# Sitara_AUX.net
KiCad netlist of a schematic drawn in Altium Designer
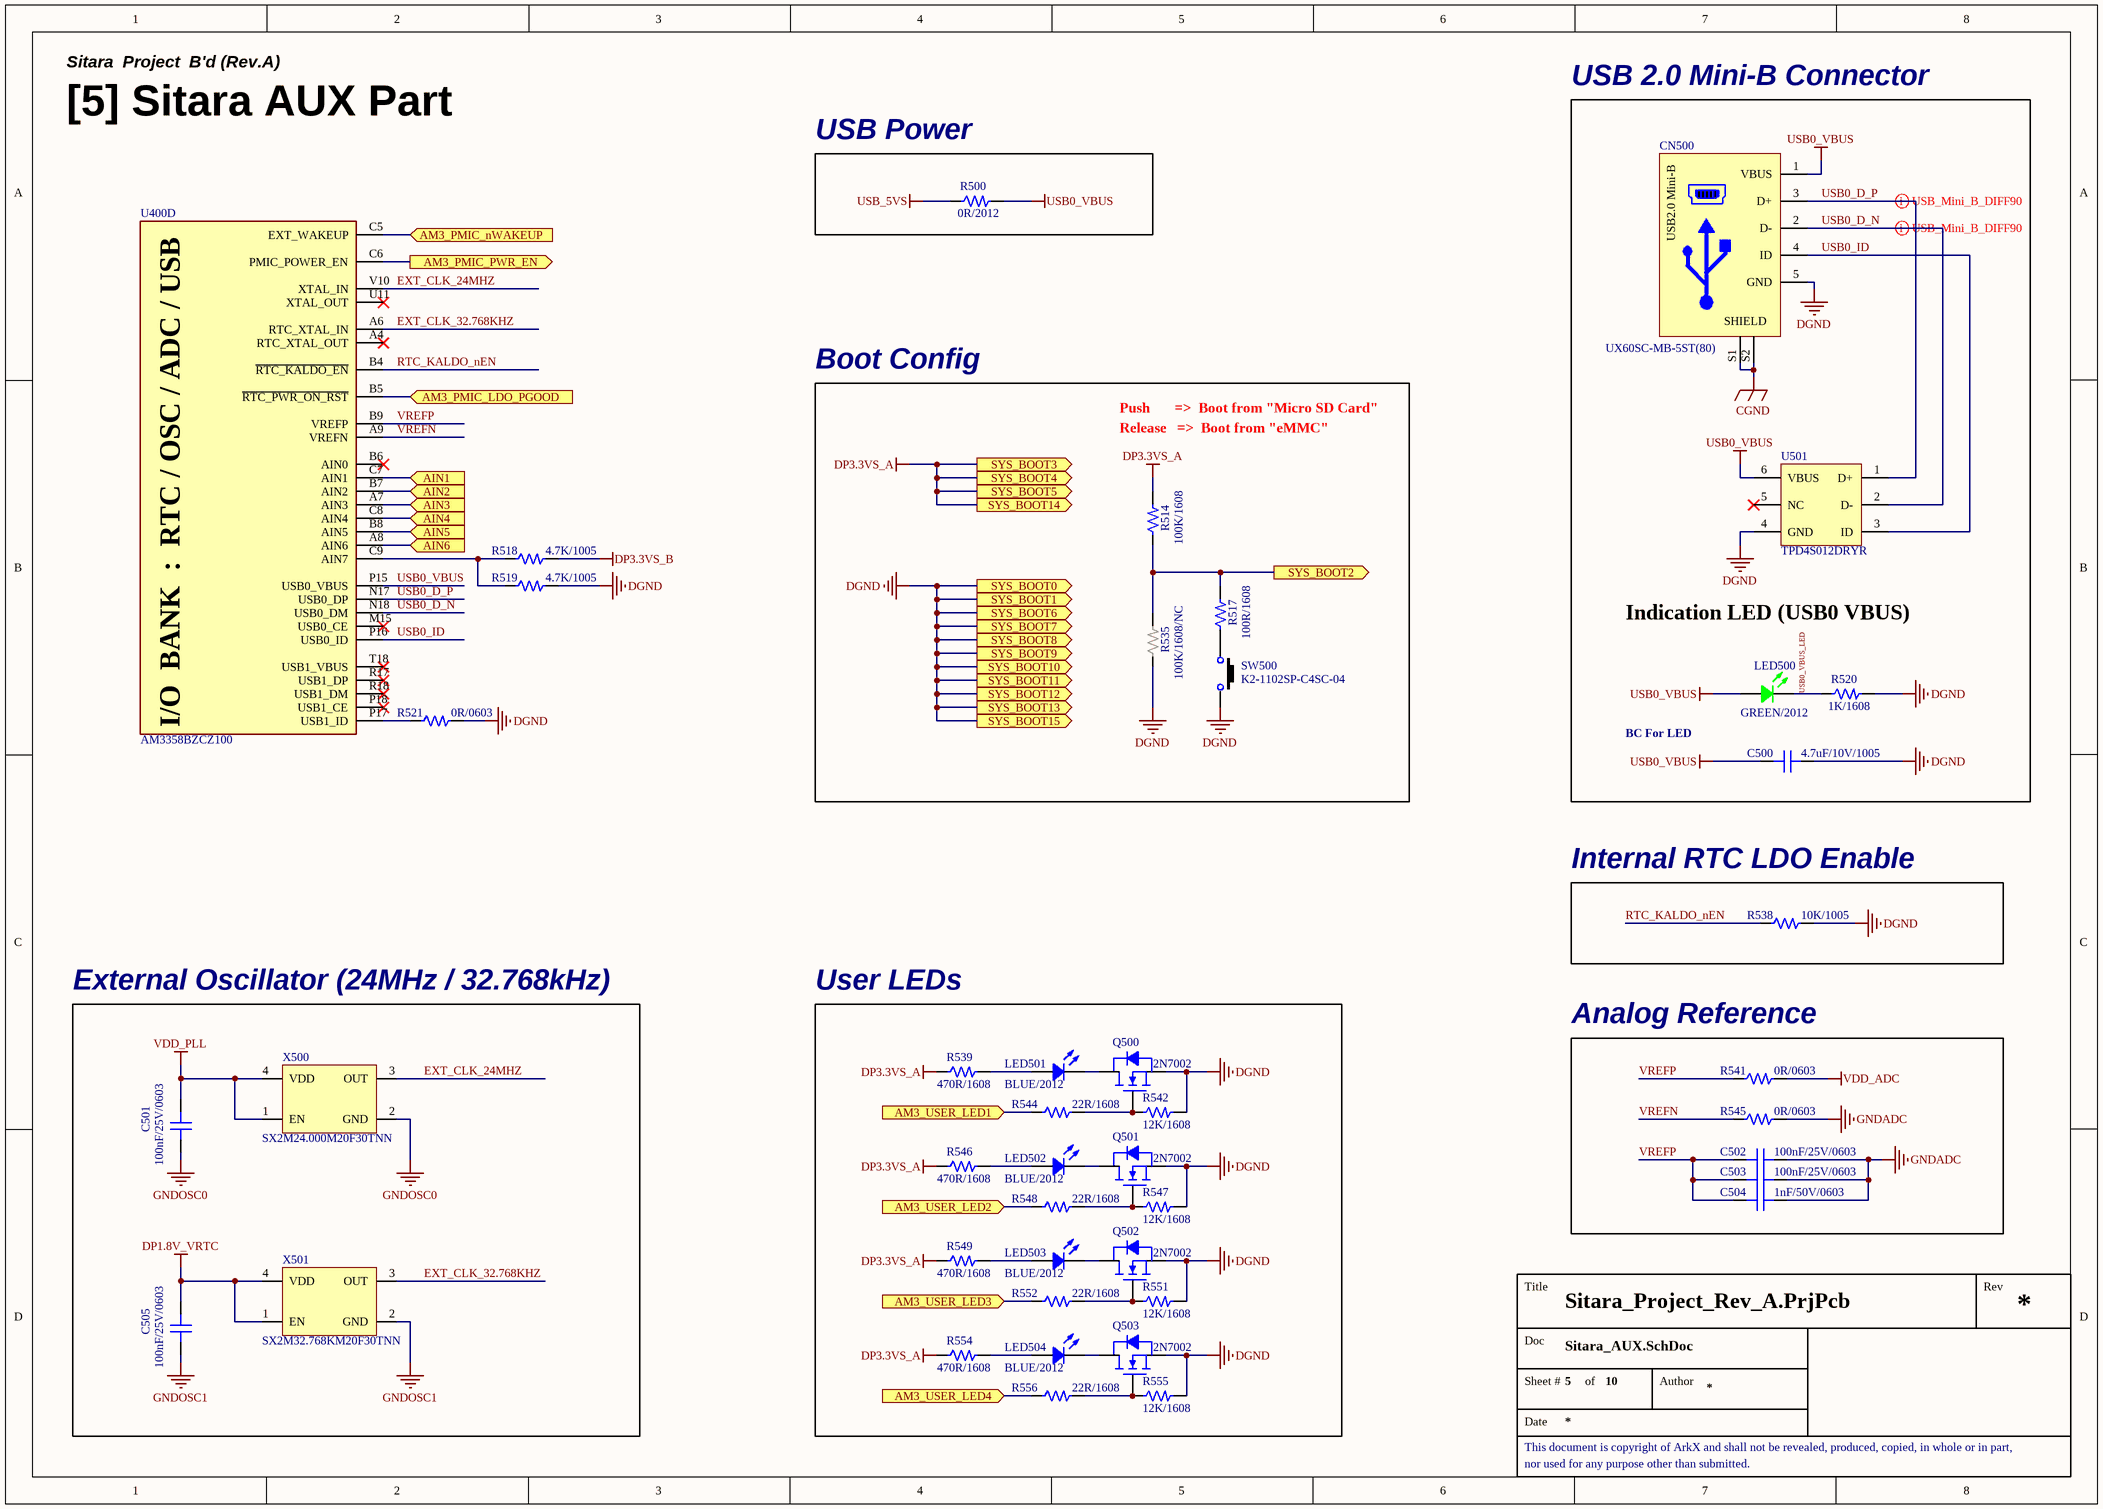
[diagram p0: Sitara_AUX.SchDoc]

(export (version "E")
  (design (tool "Eeschema 10.0.6"))
  (components
    (comp (ref "C500")
      (value "4.7uF/10V/1005")
      (footprint "CAP 1005 (0402_INCH)")
      (description "10V 4.7uF X5R ±20% 0402  Multilayer Ceramic Capacitors MLCC - SMD/SMT ROHS")
      (fields (field (name "LCSC PART #") "C23733"))
      (libsource (lib "Arkx") (part "CAP_4.7uF/10V/1005"))
    )
    (comp (ref "C501")
      (value "100nF/25V/0603")
      (footprint "CAP 0603 (0201_INCH)")
      (description "Ceramic CAP_100nF/25V/0603")
      (fields (field (name "LCSC PART #") "C181047"))
      (libsource (lib "Arkx") (part "CAP_100nF/25V/0603"))
    )
    (comp (ref "C502")
      (value "100nF/25V/0603")
      (footprint "CAP 0603 (0201_INCH)")
      (description "Ceramic CAP_100nF/25V/0603")
      (fields (field (name "LCSC PART #") "C181047"))
      (libsource (lib "Arkx") (part "CAP_100nF/25V/0603"))
    )
    (comp (ref "C503")
      (value "100nF/25V/0603")
      (footprint "CAP 0603 (0201_INCH)")
      (description "Ceramic CAP_100nF/25V/0603")
      (fields (field (name "LCSC PART #") "C181047"))
      (libsource (lib "Arkx") (part "CAP_100nF/25V/0603"))
    )
    (comp (ref "C504")
      (value "1nF/50V/0603")
      (footprint "CAP 0603 (0201_INCH)")
      (description "Ceramic CAP_1nF/50V/0603")
      (fields (field (name "LCSC PART #") "C85934"))
      (libsource (lib "Arkx") (part "CAP_1nF/50V/0603"))
    )
    (comp (ref "C505")
      (value "100nF/25V/0603")
      (footprint "CAP 0603 (0201_INCH)")
      (description "Ceramic CAP_100nF/25V/0603")
      (fields (field (name "LCSC PART #") "C181047"))
      (libsource (lib "Arkx") (part "CAP_100nF/25V/0603"))
    )
    (comp (ref "CN500")
      (value "UX60SC-MB-5ST(80)")
      (footprint "CON_USB2.0-Mini-B (UX60SC-MB-5ST(80))")
      (description "USB - mini B USB 2.0 Receptacle Connector 5 Position Surface Mount, Right Angle")
      (fields (field (name "LCSC PART #") "C2692070"))
      (libsource (lib "Arkx") (part "CON_USB2.0-Mini-B"))
    )
    (comp (ref "LED500")
      (value "GREEN/2012")
      (footprint "LED MHT170RGBCT (GREEN)")
      (fields (field (name "LCSC PART #") "C2962094"))
      (libsource (lib "Arkx") (part "LED_MHT170RGBCT(GREEN)"))
    )
    (comp (ref "LED501")
      (value "BLUE/2012")
      (footprint "LED MHT170RGBCT (BLUE)")
      (fields (field (name "LCSC PART #") "C2962094"))
      (libsource (lib "Arkx") (part "LED_MHT170RGBCT(BLUE)"))
    )
    (comp (ref "LED502")
      (value "BLUE/2012")
      (footprint "LED MHT170RGBCT (BLUE)")
      (fields (field (name "LCSC PART #") "C2962094"))
      (libsource (lib "Arkx") (part "LED_MHT170RGBCT(BLUE)"))
    )
    (comp (ref "LED503")
      (value "BLUE/2012")
      (footprint "LED MHT170RGBCT (BLUE)")
      (fields (field (name "LCSC PART #") "C2962094"))
      (libsource (lib "Arkx") (part "LED_MHT170RGBCT(BLUE)"))
    )
    (comp (ref "LED504")
      (value "BLUE/2012")
      (footprint "LED MHT170RGBCT (BLUE)")
      (fields (field (name "LCSC PART #") "C2962094"))
      (libsource (lib "Arkx") (part "LED_MHT170RGBCT(BLUE)"))
    )
    (comp (ref "Q500")
      (value "2N7002")
      (footprint "SOT 23-3 (DIODES INCORPORATED)")
      (description "60V 115mA 200mW 7.5Ω@10V,500mA N Channel SOT-23  MOSFETs ROHS")
      (fields (field (name "LCSC PART #") "C8545"))
      (libsource (lib "Arkx") (part "FET_2N7002"))
    )
    (comp (ref "Q501")
      (value "2N7002")
      (footprint "SOT 23-3 (DIODES INCORPORATED)")
      (description "60V 115mA 200mW 7.5Ω@10V,500mA N Channel SOT-23  MOSFETs ROHS")
      (fields (field (name "LCSC PART #") "C8545"))
      (libsource (lib "Arkx") (part "FET_2N7002"))
    )
    (comp (ref "Q502")
      (value "2N7002")
      (footprint "SOT 23-3 (DIODES INCORPORATED)")
      (description "60V 115mA 200mW 7.5Ω@10V,500mA N Channel SOT-23  MOSFETs ROHS")
      (fields (field (name "LCSC PART #") "C8545"))
      (libsource (lib "Arkx") (part "FET_2N7002"))
    )
    (comp (ref "Q503")
      (value "2N7002")
      (footprint "SOT 23-3 (DIODES INCORPORATED)")
      (description "60V 115mA 200mW 7.5Ω@10V,500mA N Channel SOT-23  MOSFETs ROHS")
      (fields (field (name "LCSC PART #") "C8545"))
      (libsource (lib "Arkx") (part "FET_2N7002"))
    )
    (comp (ref "R500")
      (value "0R/2012")
      (footprint "RES 2012 (0805_inch)")
      (description "RES_0R/2012/0.125W")
      (fields (field (name "LCSC PART #") "C17477"))
      (libsource (lib "Arkx") (part "RES_0R/2012/0.125W"))
    )
    (comp (ref "R514")
      (value "100K/1608")
      (footprint "RES 1608 (0603_inch)")
      (description "RES_100K/1608/0.1W")
      (fields (field (name "LCSC PART #") "C25803"))
      (libsource (lib "Arkx") (part "RES_100K/1608/0.1W"))
    )
    (comp (ref "R517")
      (value "100R/1608")
      (footprint "RES 1608 (0603_inch)")
      (description "RES_100R/1608/0.1W")
      (fields (field (name "LCSC PART #") "C22775"))
      (libsource (lib "Arkx") (part "RES_100R/1608/0.1W"))
    )
    (comp (ref "R518")
      (value "4.7K/1005")
      (footprint "RES 1005 (0402_inch)")
      (description "RES_4.7K/1005/62.5mW")
      (fields (field (name "LCSC PART #") "C25900"))
      (libsource (lib "Arkx") (part "RES_4.7K/1005/62.5mW"))
    )
    (comp (ref "R519")
      (value "4.7K/1005")
      (footprint "RES 1005 (0402_inch)")
      (description "RES_4.7K/1005/62.5mW")
      (fields (field (name "LCSC PART #") "C25900"))
      (libsource (lib "Arkx") (part "RES_4.7K/1005/62.5mW"))
    )
    (comp (ref "R520")
      (value "1K/1608")
      (footprint "RES 1608 (0603_inch)")
      (description "RES_1K/1608/0.1W")
      (fields (field (name "LCSC PART #") "C21190"))
      (libsource (lib "Arkx") (part "RES_1K/1608/0.1W"))
    )
    (comp (ref "R521")
      (value "0R/0603")
      (footprint "RES 0603 (0201_inch)")
      (description "50mW Thick Film Resistors 25V ±1% 0Ω 0201  Chip Resistor - Surface Mount ROHS")
      (fields (field (name "LCSC PART #") "C106227"))
      (libsource (lib "Arkx") (part "RES_0R/0603/50mW"))
    )
    (comp (ref "R535")
      (value "100K/1608/NC")
      (footprint "RES 1608 (0603_inch)/NC")
      (description "RES_100K/1608/0.1W")
      (libsource (lib "Arkx") (part "RES_NC_100K/1608/0.1W"))
    )
    (comp (ref "R538")
      (value "10K/1005")
      (footprint "RES 1005 (0402_inch)")
      (description "RES_10K/1005/62.5mW")
      (fields (field (name "LCSC PART #") "C25744"))
      (libsource (lib "Arkx") (part "RES_10K/1005/62.5mW"))
    )
    (comp (ref "R539")
      (value "470R/1608")
      (footprint "RES 1608 (0603_inch)")
      (description "RES_470R/1608/0.1W")
      (fields (field (name "LCSC PART #") "C23179"))
      (libsource (lib "Arkx") (part "RES_470R/1608/0.1W"))
    )
    (comp (ref "R541")
      (value "0R/0603")
      (footprint "RES 0603 (0201_inch)")
      (description "50mW Thick Film Resistors 25V ±1% 0Ω 0201  Chip Resistor - Surface Mount ROHS")
      (fields (field (name "LCSC PART #") "C106227"))
      (libsource (lib "Arkx") (part "RES_0R/0603/50mW"))
    )
    (comp (ref "R542")
      (value "12K/1608")
      (footprint "RES 1608 (0603_inch)")
      (description "RES_12K/1608/0.1W")
      (fields (field (name "LCSC PART #") "C22790"))
      (libsource (lib "Arkx") (part "RES_12K/1608/0.1W"))
    )
    (comp (ref "R544")
      (value "22R/1608")
      (footprint "RES 1608 (0603_inch)")
      (description "RES_22R/1608/0.1W")
      (fields (field (name "LCSC PART #") "C23345"))
      (libsource (lib "Arkx") (part "RES_22R/1608/0.1W"))
    )
    (comp (ref "R545")
      (value "0R/0603")
      (footprint "RES 0603 (0201_inch)")
      (description "50mW Thick Film Resistors 25V ±1% 0Ω 0201  Chip Resistor - Surface Mount ROHS")
      (fields (field (name "LCSC PART #") "C106227"))
      (libsource (lib "Arkx") (part "RES_0R/0603/50mW"))
    )
    (comp (ref "R546")
      (value "470R/1608")
      (footprint "RES 1608 (0603_inch)")
      (description "RES_470R/1608/0.1W")
      (fields (field (name "LCSC PART #") "C23179"))
      (libsource (lib "Arkx") (part "RES_470R/1608/0.1W"))
    )
    (comp (ref "R547")
      (value "12K/1608")
      (footprint "RES 1608 (0603_inch)")
      (description "RES_12K/1608/0.1W")
      (fields (field (name "LCSC PART #") "C22790"))
      (libsource (lib "Arkx") (part "RES_12K/1608/0.1W"))
    )
    (comp (ref "R548")
      (value "22R/1608")
      (footprint "RES 1608 (0603_inch)")
      (description "RES_22R/1608/0.1W")
      (fields (field (name "LCSC PART #") "C23345"))
      (libsource (lib "Arkx") (part "RES_22R/1608/0.1W"))
    )
    (comp (ref "R549")
      (value "470R/1608")
      (footprint "RES 1608 (0603_inch)")
      (description "RES_470R/1608/0.1W")
      (fields (field (name "LCSC PART #") "C23179"))
      (libsource (lib "Arkx") (part "RES_470R/1608/0.1W"))
    )
    (comp (ref "R551")
      (value "12K/1608")
      (footprint "RES 1608 (0603_inch)")
      (description "RES_12K/1608/0.1W")
      (fields (field (name "LCSC PART #") "C22790"))
      (libsource (lib "Arkx") (part "RES_12K/1608/0.1W"))
    )
    (comp (ref "R552")
      (value "22R/1608")
      (footprint "RES 1608 (0603_inch)")
      (description "RES_22R/1608/0.1W")
      (fields (field (name "LCSC PART #") "C23345"))
      (libsource (lib "Arkx") (part "RES_22R/1608/0.1W"))
    )
    (comp (ref "R554")
      (value "470R/1608")
      (footprint "RES 1608 (0603_inch)")
      (description "RES_470R/1608/0.1W")
      (fields (field (name "LCSC PART #") "C23179"))
      (libsource (lib "Arkx") (part "RES_470R/1608/0.1W"))
    )
    (comp (ref "R555")
      (value "12K/1608")
      (footprint "RES 1608 (0603_inch)")
      (description "RES_12K/1608/0.1W")
      (fields (field (name "LCSC PART #") "C22790"))
      (libsource (lib "Arkx") (part "RES_12K/1608/0.1W"))
    )
    (comp (ref "R556")
      (value "22R/1608")
      (footprint "RES 1608 (0603_inch)")
      (description "RES_22R/1608/0.1W")
      (fields (field (name "LCSC PART #") "C23345"))
      (libsource (lib "Arkx") (part "RES_22R/1608/0.1W"))
    )
    (comp (ref "SW500")
      (value "K2-1102SP-C4SC-04")
      (footprint "SW K2-1102SP-C4SC-04")
      (fields (field (name "LCSC PART #") "C127509"))
      (libsource (lib "Arkx") (part "SW_K2-1102SP-C4SC-04(2P)"))
    )
    (comp (ref "U400")
      (value "AM3358BZCZ100")
      (footprint "IC_SOC_AM3358BZCZ100")
      (description "ARM® Cortex®-A8 Microprocessor IC Sitara™ 1 Core, 32-Bit 1.0GHz 324-NFBGA (15x15)")
      (fields (field (name "LCSC PART #") "C73932"))
      (libsource (lib "Arkx") (part "IC_SOC_AM3358BZCZ100"))
    )
    (comp (ref "U501")
      (value "TPD4S012DRYR")
      (footprint "IC_SON-6")
      (description "Clamp 3A (8/20µs) Ipp Tvs Diode Surface Mount 6-SON (1.45x1)")
      (fields (field (name "LCSC PART #") "C96506"))
      (libsource (lib "Arkx") (part "DIO_TVS_TPD4S012DRYR"))
    )
    (comp (ref "X500")
      (value "SX2M24.000M20F30TNN")
      (footprint "OSC SMD_2.5x2.0 (SCTF)")
      (description "1.62V~3.63V ±20ppm 10mA ±30ppm CMOS 24MHz SMD2520-4P  Crystal Oscillators ROHS")
      (fields (field (name "LCSC PART #") "C2901600"))
      (libsource (lib "Arkx") (part "OSC_SX2M24.000M20F30TNN(24MHz)"))
    )
    (comp (ref "X501")
      (value "SX2M32.768KM20F30TNN")
      (footprint "OSC SMD_2.5x2.0 (SCTF)")
      (description "1.62V~3.63V ±20ppm 90uA ±30ppm CMOS 32.768kHz SMD2520-4P  Crystal Oscillators ROHS")
      (fields (field (name "LCSC PART #") "C2901603"))
      (libsource (lib "Arkx") (part "OSC_SX2M32.768KM20F30TNN(32.768kHz)"))
    )
  )
  (nets
    (net (code "1") (name "/AIN1") (class "Default")
      (node (ref "U400") (pin "C7") (pinfunction "AIN1_C7") (pintype "passive"))
    )
    (net (code "2") (name "/AIN2") (class "Default")
      (node (ref "U400") (pin "B7") (pinfunction "AIN2_B7") (pintype "passive"))
    )
    (net (code "3") (name "/AIN3") (class "Default")
      (node (ref "U400") (pin "A7") (pinfunction "AIN3_A7") (pintype "passive"))
    )
    (net (code "4") (name "/AIN4") (class "Default")
      (node (ref "U400") (pin "C8") (pinfunction "AIN4_C8") (pintype "passive"))
    )
    (net (code "5") (name "/AIN5") (class "Default")
      (node (ref "U400") (pin "B8") (pinfunction "AIN5_B8") (pintype "passive"))
    )
    (net (code "6") (name "/AIN6") (class "Default")
      (node (ref "U400") (pin "A8") (pinfunction "AIN6_A8") (pintype "passive"))
    )
    (net (code "7") (name "/AM3_PMIC_LDO_PGOOD") (class "Default")
      (node (ref "U400") (pin "B5") (pinfunction "~{RTC_PWR_ON_RST}_B5") (pintype "passive"))
    )
    (net (code "8") (name "/AM3_PMIC_PWR_EN") (class "Default")
      (node (ref "U400") (pin "C6") (pinfunction "PMIC_POWER_EN_C6") (pintype "passive"))
    )
    (net (code "9") (name "/AM3_PMIC_nWAKEUP") (class "Default")
      (node (ref "U400") (pin "C5") (pinfunction "EXT_WAKEUP_C5") (pintype "passive"))
    )
    (net (code "10") (name "/AM3_USER_LED1") (class "Default")
      (node (ref "R544") (pin "1") (pinfunction "1_1") (pintype "passive"))
    )
    (net (code "11") (name "/AM3_USER_LED2") (class "Default")
      (node (ref "R548") (pin "1") (pinfunction "1_1") (pintype "passive"))
    )
    (net (code "12") (name "/AM3_USER_LED3") (class "Default")
      (node (ref "R552") (pin "1") (pinfunction "1_1") (pintype "passive"))
    )
    (net (code "13") (name "/AM3_USER_LED4") (class "Default")
      (node (ref "R556") (pin "1") (pinfunction "1_1") (pintype "passive"))
    )
    (net (code "14") (name "/EXT_CLK_24MHZ") (class "Default")
      (node (ref "U400") (pin "V10") (pinfunction "XTAL_IN_V10") (pintype "passive"))
      (node (ref "X500") (pin "3") (pinfunction "OUT_3") (pintype "passive"))
    )
    (net (code "15") (name "/EXT_CLK_32.768KHZ") (class "Default")
      (node (ref "U400") (pin "A6") (pinfunction "RTC_XTAL_IN_A6") (pintype "passive"))
      (node (ref "X501") (pin "3") (pinfunction "OUT_3") (pintype "passive"))
    )
    (net (code "16") (name "/RTC_KALDO_nEN") (class "Default")
      (node (ref "R538") (pin "1") (pinfunction "1_1") (pintype "passive"))
      (node (ref "U400") (pin "B4") (pinfunction "~{RTC_KALDO_EN}_B4") (pintype "passive"))
    )
    (net (code "17") (name "/SYS_BOOT2") (class "Default")
      (node (ref "R514") (pin "1") (pinfunction "1_1") (pintype "passive"))
      (node (ref "R517") (pin "2") (pinfunction "2_2") (pintype "passive"))
      (node (ref "R535") (pin "2") (pinfunction "2_2") (pintype "passive"))
    )
    (net (code "18") (name "/USB0_D_N") (class "Default")
      (node (ref "CN500") (pin "2") (pinfunction "D-_2") (pintype "passive"))
      (node (ref "U400") (pin "N18") (pinfunction "USB0_DM_N18") (pintype "passive"))
      (node (ref "U501") (pin "2") (pinfunction "D-_2") (pintype "passive"))
    )
    (net (code "19") (name "/USB0_D_P") (class "Default")
      (node (ref "CN500") (pin "3") (pinfunction "D+_3") (pintype "passive"))
      (node (ref "U400") (pin "N17") (pinfunction "USB0_DP_N17") (pintype "passive"))
      (node (ref "U501") (pin "1") (pinfunction "D+_1") (pintype "passive"))
    )
    (net (code "20") (name "/USB0_ID") (class "Default")
      (node (ref "CN500") (pin "4") (pinfunction "ID_4") (pintype "passive"))
      (node (ref "U400") (pin "P16") (pinfunction "USB0_ID_P16") (pintype "passive"))
      (node (ref "U501") (pin "3") (pinfunction "ID_3") (pintype "passive"))
    )
    (net (code "21") (name "/USB0_VBUS_LED") (class "Default")
      (node (ref "LED500") (pin "2") (pinfunction "GREEN_2") (pintype "passive"))
      (node (ref "R520") (pin "1") (pinfunction "1_1") (pintype "passive"))
    )
    (net (code "22") (name "/VREFN") (class "Default")
      (node (ref "R545") (pin "1") (pinfunction "1_1") (pintype "passive"))
      (node (ref "U400") (pin "A9") (pinfunction "VREFN_A9") (pintype "passive"))
    )
    (net (code "23") (name "/VREFP") (class "Default")
      (node (ref "C502") (pin "1") (pinfunction "1_1") (pintype "passive"))
      (node (ref "C503") (pin "1") (pinfunction "1_1") (pintype "passive"))
      (node (ref "C504") (pin "1") (pinfunction "1_1") (pintype "passive"))
      (node (ref "R541") (pin "1") (pinfunction "1_1") (pintype "passive"))
      (node (ref "U400") (pin "B9") (pinfunction "VREFP_B9") (pintype "passive"))
    )
    (net (code "24") (name "CGND") (class "Default")
      (node (ref "CN500") (pin "S1") (pinfunction "SHIELD_S1") (pintype "passive"))
      (node (ref "CN500") (pin "S2") (pinfunction "SHIELD_S2") (pintype "passive"))
    )
    (net (code "25") (name "DGND") (class "Default")
      (node (ref "C500") (pin "2") (pinfunction "2_2") (pintype "passive"))
      (node (ref "CN500") (pin "5") (pinfunction "GND_5") (pintype "passive"))
      (node (ref "Q500") (pin "2") (pinfunction "S_2") (pintype "passive"))
      (node (ref "Q501") (pin "2") (pinfunction "S_2") (pintype "passive"))
      (node (ref "Q502") (pin "2") (pinfunction "S_2") (pintype "passive"))
      (node (ref "Q503") (pin "2") (pinfunction "S_2") (pintype "passive"))
      (node (ref "R519") (pin "2") (pinfunction "2_2") (pintype "passive"))
      (node (ref "R520") (pin "2") (pinfunction "2_2") (pintype "passive"))
      (node (ref "R521") (pin "2") (pinfunction "2_2") (pintype "passive"))
      (node (ref "R535") (pin "1") (pinfunction "1_1") (pintype "passive"))
      (node (ref "R538") (pin "2") (pinfunction "2_2") (pintype "passive"))
      (node (ref "R542") (pin "2") (pinfunction "2_2") (pintype "passive"))
      (node (ref "R547") (pin "2") (pinfunction "2_2") (pintype "passive"))
      (node (ref "R551") (pin "2") (pinfunction "2_2") (pintype "passive"))
      (node (ref "R555") (pin "2") (pinfunction "2_2") (pintype "passive"))
      (node (ref "SW500") (pin "3") (pinfunction "3_3") (pintype "passive"))
      (node (ref "U501") (pin "4") (pinfunction "GND_4") (pintype "passive"))
    )
    (net (code "26") (name "DP1.8V_VRTC") (class "Default")
      (node (ref "C505") (pin "2") (pinfunction "2_2") (pintype "passive"))
      (node (ref "X501") (pin "1") (pinfunction "EN_1") (pintype "passive"))
      (node (ref "X501") (pin "4") (pinfunction "VDD_4") (pintype "passive"))
    )
    (net (code "27") (name "DP3.3VS_A") (class "Default")
      (node (ref "R514") (pin "2") (pinfunction "2_2") (pintype "passive"))
      (node (ref "R539") (pin "1") (pinfunction "1_1") (pintype "passive"))
      (node (ref "R546") (pin "1") (pinfunction "1_1") (pintype "passive"))
      (node (ref "R549") (pin "1") (pinfunction "1_1") (pintype "passive"))
      (node (ref "R554") (pin "1") (pinfunction "1_1") (pintype "passive"))
    )
    (net (code "28") (name "DP3.3VS_B") (class "Default")
      (node (ref "R518") (pin "2") (pinfunction "2_2") (pintype "passive"))
    )
    (net (code "29") (name "GNDADC") (class "Default")
      (node (ref "C502") (pin "2") (pinfunction "2_2") (pintype "passive"))
      (node (ref "C503") (pin "2") (pinfunction "2_2") (pintype "passive"))
      (node (ref "C504") (pin "2") (pinfunction "2_2") (pintype "passive"))
      (node (ref "R545") (pin "2") (pinfunction "2_2") (pintype "passive"))
    )
    (net (code "30") (name "GNDOSC0") (class "Default")
      (node (ref "C501") (pin "1") (pinfunction "1_1") (pintype "passive"))
      (node (ref "X500") (pin "2") (pinfunction "GND_2") (pintype "passive"))
    )
    (net (code "31") (name "GNDOSC1") (class "Default")
      (node (ref "C505") (pin "1") (pinfunction "1_1") (pintype "passive"))
      (node (ref "X501") (pin "2") (pinfunction "GND_2") (pintype "passive"))
    )
    (net (code "32") (name "Net-(LED501-BLUE)") (class "Default")
      (node (ref "LED501") (pin "3") (pinfunction "BLUE_3") (pintype "passive"))
      (node (ref "Q500") (pin "3") (pinfunction "D_3") (pintype "passive"))
    )
    (net (code "33") (name "Net-(LED501-Common_Anode)") (class "Default")
      (node (ref "LED501") (pin "4") (pinfunction "Common_Anode_4") (pintype "passive"))
      (node (ref "R539") (pin "2") (pinfunction "2_2") (pintype "passive"))
    )
    (net (code "34") (name "Net-(LED502-BLUE)") (class "Default")
      (node (ref "LED502") (pin "3") (pinfunction "BLUE_3") (pintype "passive"))
      (node (ref "Q501") (pin "3") (pinfunction "D_3") (pintype "passive"))
    )
    (net (code "35") (name "Net-(LED502-Common_Anode)") (class "Default")
      (node (ref "LED502") (pin "4") (pinfunction "Common_Anode_4") (pintype "passive"))
      (node (ref "R546") (pin "2") (pinfunction "2_2") (pintype "passive"))
    )
    (net (code "36") (name "Net-(LED503-BLUE)") (class "Default")
      (node (ref "LED503") (pin "3") (pinfunction "BLUE_3") (pintype "passive"))
      (node (ref "Q502") (pin "3") (pinfunction "D_3") (pintype "passive"))
    )
    (net (code "37") (name "Net-(LED503-Common_Anode)") (class "Default")
      (node (ref "LED503") (pin "4") (pinfunction "Common_Anode_4") (pintype "passive"))
      (node (ref "R549") (pin "2") (pinfunction "2_2") (pintype "passive"))
    )
    (net (code "38") (name "Net-(LED504-BLUE)") (class "Default")
      (node (ref "LED504") (pin "3") (pinfunction "BLUE_3") (pintype "passive"))
      (node (ref "Q503") (pin "3") (pinfunction "D_3") (pintype "passive"))
    )
    (net (code "39") (name "Net-(LED504-Common_Anode)") (class "Default")
      (node (ref "LED504") (pin "4") (pinfunction "Common_Anode_4") (pintype "passive"))
      (node (ref "R554") (pin "2") (pinfunction "2_2") (pintype "passive"))
    )
    (net (code "40") (name "Net-(Q500-G)") (class "Default")
      (node (ref "Q500") (pin "1") (pinfunction "G_1") (pintype "passive"))
      (node (ref "R542") (pin "1") (pinfunction "1_1") (pintype "passive"))
      (node (ref "R544") (pin "2") (pinfunction "2_2") (pintype "passive"))
    )
    (net (code "41") (name "Net-(Q501-G)") (class "Default")
      (node (ref "Q501") (pin "1") (pinfunction "G_1") (pintype "passive"))
      (node (ref "R547") (pin "1") (pinfunction "1_1") (pintype "passive"))
      (node (ref "R548") (pin "2") (pinfunction "2_2") (pintype "passive"))
    )
    (net (code "42") (name "Net-(Q502-G)") (class "Default")
      (node (ref "Q502") (pin "1") (pinfunction "G_1") (pintype "passive"))
      (node (ref "R551") (pin "1") (pinfunction "1_1") (pintype "passive"))
      (node (ref "R552") (pin "2") (pinfunction "2_2") (pintype "passive"))
    )
    (net (code "43") (name "Net-(Q503-G)") (class "Default")
      (node (ref "Q503") (pin "1") (pinfunction "G_1") (pintype "passive"))
      (node (ref "R555") (pin "1") (pinfunction "1_1") (pintype "passive"))
      (node (ref "R556") (pin "2") (pinfunction "2_2") (pintype "passive"))
    )
    (net (code "44") (name "Net-(R517-Pad1)") (class "Default")
      (node (ref "R517") (pin "1") (pinfunction "1_1") (pintype "passive"))
      (node (ref "SW500") (pin "1") (pinfunction "1_1") (pintype "passive"))
    )
    (net (code "45") (name "Net-(U400D-AIN7)") (class "Default")
      (node (ref "R518") (pin "1") (pinfunction "1_1") (pintype "passive"))
      (node (ref "R519") (pin "1") (pinfunction "1_1") (pintype "passive"))
      (node (ref "U400") (pin "C9") (pinfunction "AIN7_C9") (pintype "passive"))
    )
    (net (code "46") (name "Net-(U400D-USB1_ID)") (class "Default")
      (node (ref "R521") (pin "1") (pinfunction "1_1") (pintype "passive"))
      (node (ref "U400") (pin "P17") (pinfunction "USB1_ID_P17") (pintype "passive"))
    )
    (net (code "47") (name "USB0_VBUS") (class "Default")
      (node (ref "C500") (pin "1") (pinfunction "1_1") (pintype "passive"))
      (node (ref "CN500") (pin "1") (pinfunction "VBUS_1") (pintype "passive"))
      (node (ref "LED500") (pin "4") (pinfunction "Common_Anode_4") (pintype "passive"))
      (node (ref "R500") (pin "2") (pinfunction "2_2") (pintype "passive"))
      (node (ref "U400") (pin "P15") (pinfunction "USB0_VBUS_P15") (pintype "passive"))
      (node (ref "U501") (pin "6") (pinfunction "VBUS_6") (pintype "passive"))
    )
    (net (code "48") (name "USB_5VS") (class "Default")
      (node (ref "R500") (pin "1") (pinfunction "1_1") (pintype "passive"))
    )
    (net (code "49") (name "VDD_ADC") (class "Default")
      (node (ref "R541") (pin "2") (pinfunction "2_2") (pintype "passive"))
    )
    (net (code "50") (name "VDD_PLL") (class "Default")
      (node (ref "C501") (pin "2") (pinfunction "2_2") (pintype "passive"))
      (node (ref "X500") (pin "1") (pinfunction "EN_1") (pintype "passive"))
      (node (ref "X500") (pin "4") (pinfunction "VDD_4") (pintype "passive"))
    )
    (net (code "51") (name "unconnected-(U400D-AIN0-PadB6)") (class "Default")
      (node (ref "U400") (pin "B6") (pinfunction "AIN0_B6") (pintype "passive+no_connect"))
    )
    (net (code "52") (name "unconnected-(U400D-RTC_XTAL_OUT-PadA4)") (class "Default")
      (node (ref "U400") (pin "A4") (pinfunction "RTC_XTAL_OUT_A4") (pintype "passive+no_connect"))
    )
    (net (code "53") (name "unconnected-(U400D-USB0_CE-PadM15)") (class "Default")
      (node (ref "U400") (pin "M15") (pinfunction "USB0_CE_M15") (pintype "passive+no_connect"))
    )
    (net (code "54") (name "unconnected-(U400D-USB1_CE-PadP18)") (class "Default")
      (node (ref "U400") (pin "P18") (pinfunction "USB1_CE_P18") (pintype "passive+no_connect"))
    )
    (net (code "55") (name "unconnected-(U400D-USB1_DM-PadR18)") (class "Default")
      (node (ref "U400") (pin "R18") (pinfunction "USB1_DM_R18") (pintype "passive+no_connect"))
    )
    (net (code "56") (name "unconnected-(U400D-USB1_DP-PadR17)") (class "Default")
      (node (ref "U400") (pin "R17") (pinfunction "USB1_DP_R17") (pintype "passive+no_connect"))
    )
    (net (code "57") (name "unconnected-(U400D-USB1_VBUS-PadT18)") (class "Default")
      (node (ref "U400") (pin "T18") (pinfunction "USB1_VBUS_T18") (pintype "passive+no_connect"))
    )
    (net (code "58") (name "unconnected-(U400D-XTAL_OUT-PadU11)") (class "Default")
      (node (ref "U400") (pin "U11") (pinfunction "XTAL_OUT_U11") (pintype "passive+no_connect"))
    )
    (net (code "59") (name "unconnected-(U501-NC-Pad5)") (class "Default")
      (node (ref "U501") (pin "5") (pinfunction "NC_5") (pintype "passive+no_connect"))
    )
  )
)
